# SH_HALF_ab_3.net
KiCad netlist of a schematic drawn in EAGLE
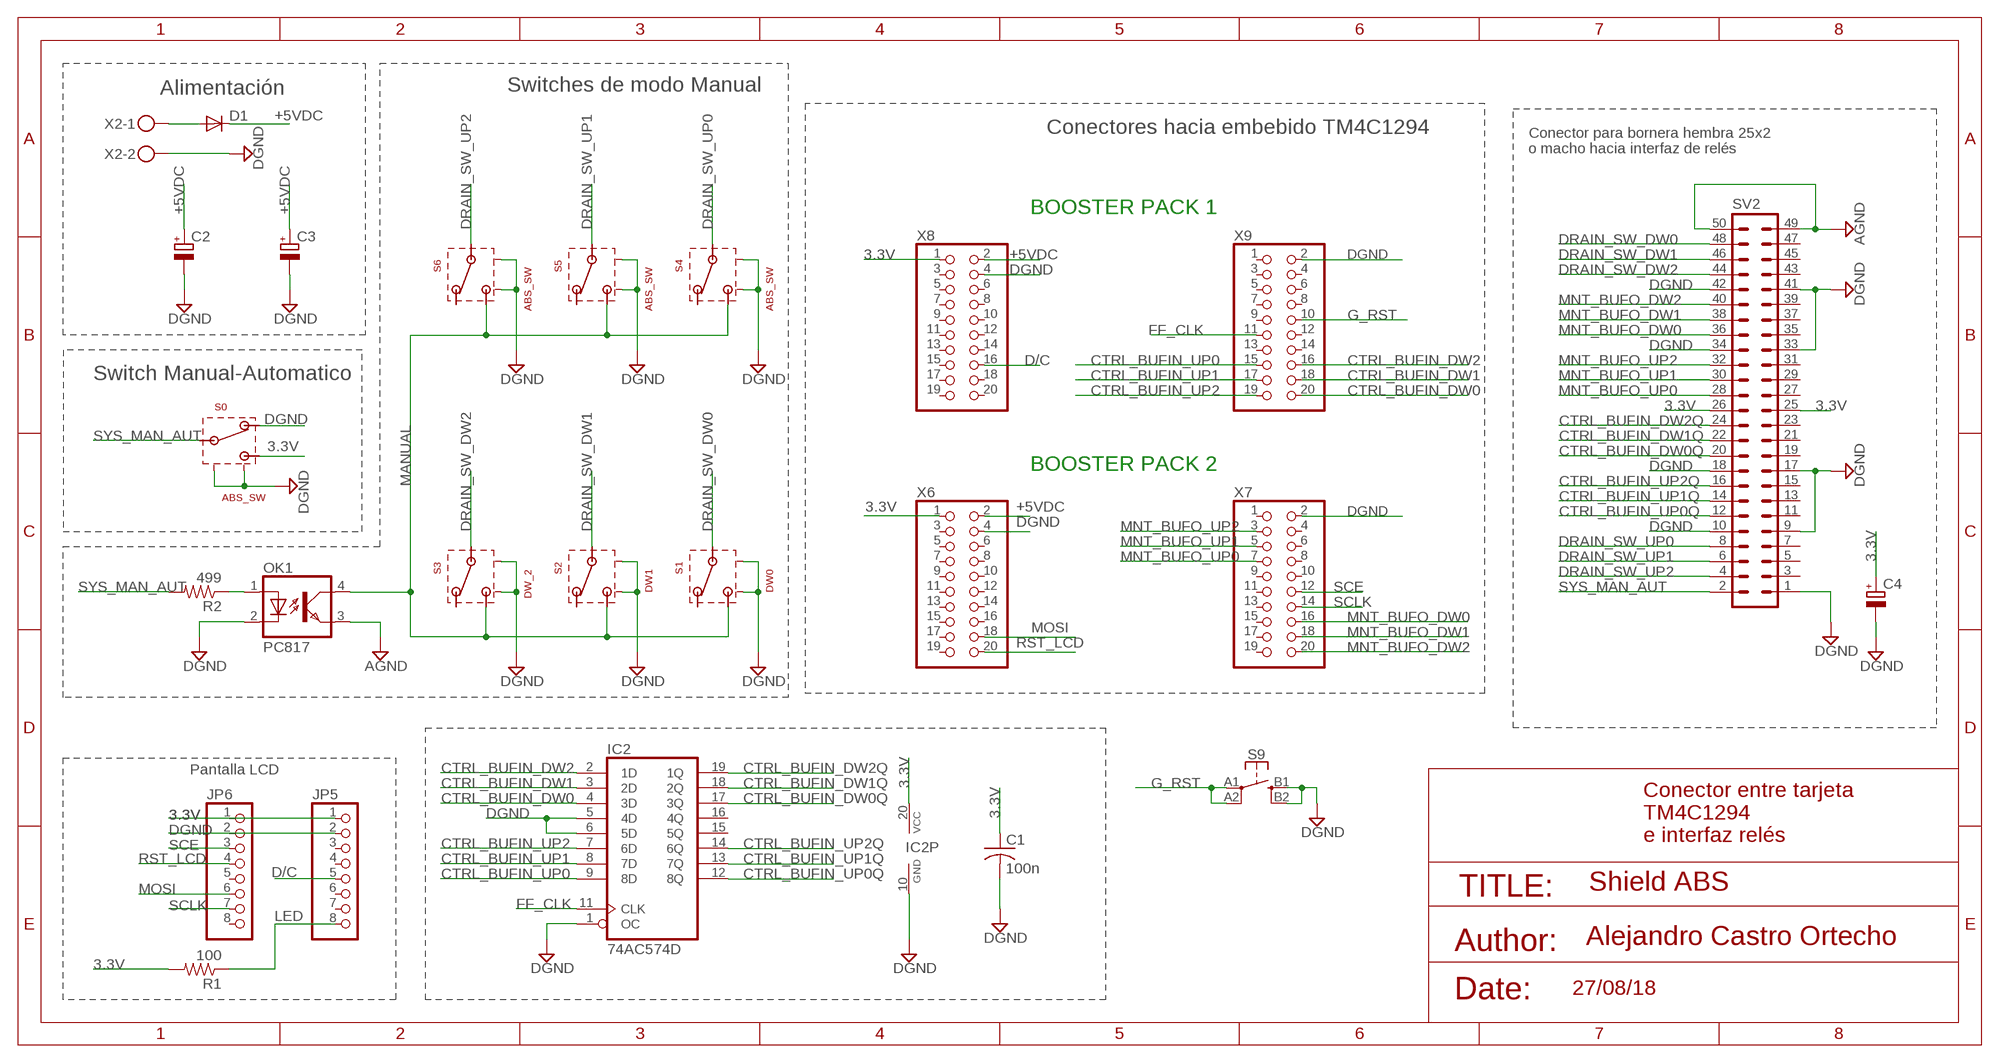
[diagram p0: schematic, sheet 1]

(export (version "E")
  (design (tool "Eeschema 10.0.6"))
  (components
    (comp (ref "C1")
      (value "100n")
      (footprint "eagle-import:C0805K")
      (libsource (lib "eagle-import") (part "C-USC0805K"))
    )
    (comp (ref "C2")
      (value "CPOL-EUB/3528-21R")
      (footprint "eagle-import:B_3528-21R")
      (libsource (lib "eagle-import") (part "CPOL-EUB/3528-21R"))
    )
    (comp (ref "C3")
      (value "CPOL-EUB/3528-21R")
      (footprint "eagle-import:B_3528-21R")
      (libsource (lib "eagle-import") (part "CPOL-EUB/3528-21R"))
    )
    (comp (ref "C4")
      (value "CPOL-EUB/3528-21R")
      (footprint "eagle-import:B_3528-21R")
      (libsource (lib "eagle-import") (part "CPOL-EUB/3528-21R"))
    )
    (comp (ref "D1")
      (value "DIODE-SMBSMB")
      (footprint "eagle-import:SMB")
      (fields (field (name "MANF") "Diodes Incorporated"))
      (libsource (lib "eagle-import") (part "DIODE-SMBSMB"))
    )
    (comp (ref "IC2")
      (value "74AC574D")
      (footprint "eagle-import:SO20W")
      (libsource (lib "eagle-import") (part "74574DAC"))
    )
    (comp (ref "JP5")
      (value "PINHD-1X8")
      (footprint "eagle-import:1X08")
      (libsource (lib "eagle-import") (part "PINHD-1X8"))
    )
    (comp (ref "JP6")
      (value "PINHD-1X8")
      (footprint "eagle-import:1X08")
      (libsource (lib "eagle-import") (part "PINHD-1X8"))
    )
    (comp (ref "OK1")
      (value "PC817")
      (footprint "eagle-import:DIL04")
      (fields (field (name "MPN") "PC817X4J000F"))
      (libsource (lib "eagle-import") (part "PC817"))
    )
    (comp (ref "R1")
      (value "100")
      (footprint "eagle-import:R1206")
      (libsource (lib "eagle-import") (part "R-US_R1206"))
    )
    (comp (ref "R2")
      (value "499")
      (footprint "eagle-import:R1206")
      (libsource (lib "eagle-import") (part "R-US_R1206"))
    )
    (comp (ref "S0")
      (value "ABS_SW")
      (footprint "eagle-import:ABS_SW")
      (libsource (lib "eagle-import") (part "ABS_SW"))
    )
    (comp (ref "S1")
      (value "DW0")
      (footprint "eagle-import:ABS_SW")
      (libsource (lib "eagle-import") (part "ABS_SW"))
    )
    (comp (ref "S2")
      (value "DW1")
      (footprint "eagle-import:ABS_SW")
      (libsource (lib "eagle-import") (part "ABS_SW"))
    )
    (comp (ref "S3")
      (value "DW_2")
      (footprint "eagle-import:ABS_SW")
      (libsource (lib "eagle-import") (part "ABS_SW"))
    )
    (comp (ref "S4")
      (value "ABS_SW")
      (footprint "eagle-import:ABS_SW")
      (libsource (lib "eagle-import") (part "ABS_SW"))
    )
    (comp (ref "S5")
      (value "ABS_SW")
      (footprint "eagle-import:ABS_SW")
      (libsource (lib "eagle-import") (part "ABS_SW"))
    )
    (comp (ref "S6")
      (value "ABS_SW")
      (footprint "eagle-import:ABS_SW")
      (libsource (lib "eagle-import") (part "ABS_SW"))
    )
    (comp (ref "S9")
      (value "MOMENTARY-SWITCH-SPST-2")
      (footprint "eagle-import:TACTILE_SWITCH_SMD_6.2MM_TALL")
      (libsource (lib "eagle-import") (part "MOMENTARY-SWITCH-SPST-2"))
    )
    (comp (ref "SV2")
      (value "ML50F")
      (footprint "eagle-import:ML50_F")
      (libsource (lib "eagle-import") (part "ML50F"))
    )
    (comp (ref "X2")
      (value "MKDSN1,5/2-5,08")
      (footprint "eagle-import:MKDSN1,5_2-5,08")
      (libsource (lib "eagle-import") (part "MKDSN1,5/2-5,08"))
    )
    (comp (ref "X6")
      (value "PINHD-2X10")
      (footprint "eagle-import:2X10")
      (libsource (lib "eagle-import") (part "PINHD-2X10"))
    )
    (comp (ref "X7")
      (value "PINHD-2X10")
      (footprint "eagle-import:2X10")
      (libsource (lib "eagle-import") (part "PINHD-2X10"))
    )
    (comp (ref "X8")
      (value "PINHD-2X10")
      (footprint "eagle-import:2X10")
      (libsource (lib "eagle-import") (part "PINHD-2X10"))
    )
    (comp (ref "X9")
      (value "PINHD-2X10")
      (footprint "eagle-import:2X10")
      (libsource (lib "eagle-import") (part "PINHD-2X10"))
    )
  )
  (nets
    (net (code "1") (name "/+5VDC") (class "Default")
      (node (ref "C2") (pin "+") (pinfunction "+_+") (pintype "passive"))
      (node (ref "C3") (pin "+") (pinfunction "+_+") (pintype "passive"))
      (node (ref "D1") (pin "C") (pinfunction "C_C") (pintype "passive"))
      (node (ref "X6") (pin "2") (pinfunction "2_2") (pintype "passive"))
      (node (ref "X8") (pin "2") (pinfunction "2_2") (pintype "passive"))
    )
    (net (code "2") (name "/3.3V") (class "Default")
      (node (ref "C1") (pin "1") (pinfunction "1_1") (pintype "passive"))
      (node (ref "C4") (pin "+") (pinfunction "+_+") (pintype "passive"))
      (node (ref "IC2") (pin "20") (pinfunction "VCC_20") (pintype "power_in"))
      (node (ref "JP5") (pin "1") (pinfunction "1_1") (pintype "passive"))
      (node (ref "JP6") (pin "1") (pinfunction "1_1") (pintype "passive"))
      (node (ref "R1") (pin "2") (pinfunction "2_2") (pintype "passive"))
      (node (ref "S0") (pin "3") (pinfunction "3_3") (pintype "bidirectional"))
      (node (ref "SV2") (pin "25") (pinfunction "25_25") (pintype "passive"))
      (node (ref "SV2") (pin "26") (pinfunction "26_26") (pintype "passive"))
      (node (ref "X6") (pin "1") (pinfunction "1_1") (pintype "passive"))
      (node (ref "X8") (pin "1") (pinfunction "1_1") (pintype "passive"))
    )
    (net (code "3") (name "/CTRL_BUFIN_DW0") (class "Default")
      (node (ref "IC2") (pin "4") (pinfunction "3D_4") (pintype "input"))
      (node (ref "X9") (pin "20") (pinfunction "20_20") (pintype "passive"))
    )
    (net (code "4") (name "/CTRL_BUFIN_DW0Q") (class "Default")
      (node (ref "IC2") (pin "17") (pinfunction "3Q_17") (pintype "tri_state"))
      (node (ref "SV2") (pin "20") (pinfunction "20_20") (pintype "passive"))
    )
    (net (code "5") (name "/CTRL_BUFIN_DW1") (class "Default")
      (node (ref "IC2") (pin "3") (pinfunction "2D_3") (pintype "input"))
      (node (ref "X9") (pin "18") (pinfunction "18_18") (pintype "passive"))
    )
    (net (code "6") (name "/CTRL_BUFIN_DW1Q") (class "Default")
      (node (ref "IC2") (pin "18") (pinfunction "2Q_18") (pintype "tri_state"))
      (node (ref "SV2") (pin "22") (pinfunction "22_22") (pintype "passive"))
    )
    (net (code "7") (name "/CTRL_BUFIN_DW2") (class "Default")
      (node (ref "IC2") (pin "2") (pinfunction "1D_2") (pintype "input"))
      (node (ref "X9") (pin "16") (pinfunction "16_16") (pintype "passive"))
    )
    (net (code "8") (name "/CTRL_BUFIN_DW2Q") (class "Default")
      (node (ref "IC2") (pin "19") (pinfunction "1Q_19") (pintype "tri_state"))
      (node (ref "SV2") (pin "24") (pinfunction "24_24") (pintype "passive"))
    )
    (net (code "9") (name "/CTRL_BUFIN_UP0") (class "Default")
      (node (ref "IC2") (pin "9") (pinfunction "8D_9") (pintype "input"))
      (node (ref "X9") (pin "15") (pinfunction "15_15") (pintype "passive"))
    )
    (net (code "10") (name "/CTRL_BUFIN_UP0Q") (class "Default")
      (node (ref "IC2") (pin "12") (pinfunction "8Q_12") (pintype "tri_state"))
      (node (ref "SV2") (pin "12") (pinfunction "12_12") (pintype "passive"))
    )
    (net (code "11") (name "/CTRL_BUFIN_UP1") (class "Default")
      (node (ref "IC2") (pin "8") (pinfunction "7D_8") (pintype "input"))
      (node (ref "X9") (pin "17") (pinfunction "17_17") (pintype "passive"))
    )
    (net (code "12") (name "/CTRL_BUFIN_UP1Q") (class "Default")
      (node (ref "IC2") (pin "13") (pinfunction "7Q_13") (pintype "tri_state"))
      (node (ref "SV2") (pin "14") (pinfunction "14_14") (pintype "passive"))
    )
    (net (code "13") (name "/CTRL_BUFIN_UP2") (class "Default")
      (node (ref "IC2") (pin "7") (pinfunction "6D_7") (pintype "input"))
      (node (ref "X9") (pin "19") (pinfunction "19_19") (pintype "passive"))
    )
    (net (code "14") (name "/CTRL_BUFIN_UP2Q") (class "Default")
      (node (ref "IC2") (pin "14") (pinfunction "6Q_14") (pintype "tri_state"))
      (node (ref "SV2") (pin "16") (pinfunction "16_16") (pintype "passive"))
    )
    (net (code "15") (name "/DRAIN_SW_DW0") (class "Default")
      (node (ref "S1") (pin "2") (pinfunction "2_2") (pintype "bidirectional"))
      (node (ref "SV2") (pin "48") (pinfunction "48_48") (pintype "passive"))
    )
    (net (code "16") (name "/DRAIN_SW_DW1") (class "Default")
      (node (ref "S2") (pin "2") (pinfunction "2_2") (pintype "bidirectional"))
      (node (ref "SV2") (pin "46") (pinfunction "46_46") (pintype "passive"))
    )
    (net (code "17") (name "/DRAIN_SW_DW2") (class "Default")
      (node (ref "S3") (pin "2") (pinfunction "2_2") (pintype "bidirectional"))
      (node (ref "SV2") (pin "44") (pinfunction "44_44") (pintype "passive"))
    )
    (net (code "18") (name "/DRAIN_SW_UP0") (class "Default")
      (node (ref "S4") (pin "2") (pinfunction "2_2") (pintype "bidirectional"))
      (node (ref "SV2") (pin "8") (pinfunction "8_8") (pintype "passive"))
    )
    (net (code "19") (name "/DRAIN_SW_UP1") (class "Default")
      (node (ref "S5") (pin "2") (pinfunction "2_2") (pintype "bidirectional"))
      (node (ref "SV2") (pin "6") (pinfunction "6_6") (pintype "passive"))
    )
    (net (code "20") (name "/DRAIN_SW_UP2") (class "Default")
      (node (ref "S6") (pin "2") (pinfunction "2_2") (pintype "bidirectional"))
      (node (ref "SV2") (pin "4") (pinfunction "4_4") (pintype "passive"))
    )
    (net (code "21") (name "/D{slash}C") (class "Default")
      (node (ref "JP5") (pin "5") (pinfunction "5_5") (pintype "passive"))
      (node (ref "X8") (pin "16") (pinfunction "16_16") (pintype "passive"))
    )
    (net (code "22") (name "/FF_CLK") (class "Default")
      (node (ref "IC2") (pin "11") (pinfunction "CLK_11") (pintype "input"))
      (node (ref "X9") (pin "11") (pinfunction "11_11") (pintype "passive"))
    )
    (net (code "23") (name "/G_RST") (class "Default")
      (node (ref "S9") (pin "A1") (pinfunction "1_A1") (pintype "passive"))
      (node (ref "S9") (pin "A2") (pinfunction "2_A2") (pintype "passive"))
      (node (ref "X9") (pin "10") (pinfunction "10_10") (pintype "passive"))
    )
    (net (code "24") (name "/LED") (class "Default")
      (node (ref "JP5") (pin "8") (pinfunction "8_8") (pintype "passive"))
      (node (ref "R1") (pin "1") (pinfunction "1_1") (pintype "passive"))
    )
    (net (code "25") (name "/MANUAL") (class "Default")
      (node (ref "OK1") (pin "4") (pinfunction "COL_4") (pintype "passive"))
      (node (ref "S1") (pin "3") (pinfunction "3_3") (pintype "bidirectional"))
      (node (ref "S2") (pin "3") (pinfunction "3_3") (pintype "bidirectional"))
      (node (ref "S3") (pin "3") (pinfunction "3_3") (pintype "bidirectional"))
      (node (ref "S4") (pin "3") (pinfunction "3_3") (pintype "bidirectional"))
      (node (ref "S5") (pin "3") (pinfunction "3_3") (pintype "bidirectional"))
      (node (ref "S6") (pin "3") (pinfunction "3_3") (pintype "bidirectional"))
    )
    (net (code "26") (name "/MNT_BUFO_DW0") (class "Default")
      (node (ref "SV2") (pin "36") (pinfunction "36_36") (pintype "passive"))
      (node (ref "X7") (pin "16") (pinfunction "16_16") (pintype "passive"))
    )
    (net (code "27") (name "/MNT_BUFO_DW1") (class "Default")
      (node (ref "SV2") (pin "38") (pinfunction "38_38") (pintype "passive"))
      (node (ref "X7") (pin "18") (pinfunction "18_18") (pintype "passive"))
    )
    (net (code "28") (name "/MNT_BUFO_DW2") (class "Default")
      (node (ref "SV2") (pin "40") (pinfunction "40_40") (pintype "passive"))
      (node (ref "X7") (pin "20") (pinfunction "20_20") (pintype "passive"))
    )
    (net (code "29") (name "/MNT_BUFO_UP0") (class "Default")
      (node (ref "SV2") (pin "28") (pinfunction "28_28") (pintype "passive"))
      (node (ref "X7") (pin "7") (pinfunction "7_7") (pintype "passive"))
    )
    (net (code "30") (name "/MNT_BUFO_UP1") (class "Default")
      (node (ref "SV2") (pin "30") (pinfunction "30_30") (pintype "passive"))
      (node (ref "X7") (pin "5") (pinfunction "5_5") (pintype "passive"))
    )
    (net (code "31") (name "/MNT_BUFO_UP2") (class "Default")
      (node (ref "SV2") (pin "32") (pinfunction "32_32") (pintype "passive"))
      (node (ref "X7") (pin "3") (pinfunction "3_3") (pintype "passive"))
    )
    (net (code "32") (name "/MOSI") (class "Default")
      (node (ref "JP6") (pin "6") (pinfunction "6_6") (pintype "passive"))
      (node (ref "X6") (pin "18") (pinfunction "18_18") (pintype "passive"))
    )
    (net (code "33") (name "/RST_LCD") (class "Default")
      (node (ref "JP6") (pin "4") (pinfunction "4_4") (pintype "passive"))
      (node (ref "X6") (pin "20") (pinfunction "20_20") (pintype "passive"))
    )
    (net (code "34") (name "/SCE") (class "Default")
      (node (ref "JP6") (pin "3") (pinfunction "3_3") (pintype "passive"))
      (node (ref "X7") (pin "12") (pinfunction "12_12") (pintype "passive"))
    )
    (net (code "35") (name "/SCLK") (class "Default")
      (node (ref "JP6") (pin "7") (pinfunction "7_7") (pintype "passive"))
      (node (ref "X7") (pin "14") (pinfunction "14_14") (pintype "passive"))
    )
    (net (code "36") (name "/SYS_MAN_AUT") (class "Default")
      (node (ref "R2") (pin "2") (pinfunction "2_2") (pintype "passive"))
      (node (ref "S0") (pin "2") (pinfunction "2_2") (pintype "bidirectional"))
      (node (ref "SV2") (pin "2") (pinfunction "2_2") (pintype "passive"))
    )
    (net (code "37") (name "AGND") (class "Default")
      (node (ref "OK1") (pin "3") (pinfunction "EMIT_3") (pintype "passive"))
      (node (ref "SV2") (pin "49") (pinfunction "49_49") (pintype "passive"))
      (node (ref "SV2") (pin "50") (pinfunction "50_50") (pintype "passive"))
    )
    (net (code "38") (name "DGND") (class "Default")
      (node (ref "C1") (pin "2") (pinfunction "2_2") (pintype "passive"))
      (node (ref "C2") (pin "-") (pinfunction "-_-") (pintype "passive"))
      (node (ref "C3") (pin "-") (pinfunction "-_-") (pintype "passive"))
      (node (ref "C4") (pin "-") (pinfunction "-_-") (pintype "passive"))
      (node (ref "IC2") (pin "1") (pinfunction "OC_1") (pintype "input"))
      (node (ref "IC2") (pin "10") (pinfunction "GND_10") (pintype "power_in"))
      (node (ref "IC2") (pin "5") (pinfunction "4D_5") (pintype "input"))
      (node (ref "IC2") (pin "6") (pinfunction "5D_6") (pintype "input"))
      (node (ref "JP5") (pin "2") (pinfunction "2_2") (pintype "passive"))
      (node (ref "JP6") (pin "2") (pinfunction "2_2") (pintype "passive"))
      (node (ref "OK1") (pin "2") (pinfunction "C_2") (pintype "passive"))
      (node (ref "S0") (pin "1") (pinfunction "1_1") (pintype "bidirectional"))
      (node (ref "S0") (pin "M1") (pinfunction "GND_M1") (pintype "power_in"))
      (node (ref "S0") (pin "M2") (pinfunction "GND1_M2") (pintype "power_in"))
      (node (ref "S1") (pin "M1") (pinfunction "GND_M1") (pintype "power_in"))
      (node (ref "S1") (pin "M2") (pinfunction "GND1_M2") (pintype "power_in"))
      (node (ref "S2") (pin "M1") (pinfunction "GND_M1") (pintype "power_in"))
      (node (ref "S2") (pin "M2") (pinfunction "GND1_M2") (pintype "power_in"))
      (node (ref "S3") (pin "M1") (pinfunction "GND_M1") (pintype "power_in"))
      (node (ref "S3") (pin "M2") (pinfunction "GND1_M2") (pintype "power_in"))
      (node (ref "S4") (pin "M1") (pinfunction "GND_M1") (pintype "power_in"))
      (node (ref "S4") (pin "M2") (pinfunction "GND1_M2") (pintype "power_in"))
      (node (ref "S5") (pin "M1") (pinfunction "GND_M1") (pintype "power_in"))
      (node (ref "S5") (pin "M2") (pinfunction "GND1_M2") (pintype "power_in"))
      (node (ref "S6") (pin "M1") (pinfunction "GND_M1") (pintype "power_in"))
      (node (ref "S6") (pin "M2") (pinfunction "GND1_M2") (pintype "power_in"))
      (node (ref "S9") (pin "B1") (pinfunction "3_B1") (pintype "passive"))
      (node (ref "S9") (pin "B2") (pinfunction "4_B2") (pintype "passive"))
      (node (ref "SV2") (pin "1") (pinfunction "1_1") (pintype "passive"))
      (node (ref "SV2") (pin "10") (pinfunction "10_10") (pintype "passive"))
      (node (ref "SV2") (pin "17") (pinfunction "17_17") (pintype "passive"))
      (node (ref "SV2") (pin "18") (pinfunction "18_18") (pintype "passive"))
      (node (ref "SV2") (pin "33") (pinfunction "33_33") (pintype "passive"))
      (node (ref "SV2") (pin "34") (pinfunction "34_34") (pintype "passive"))
      (node (ref "SV2") (pin "41") (pinfunction "41_41") (pintype "passive"))
      (node (ref "SV2") (pin "42") (pinfunction "42_42") (pintype "passive"))
      (node (ref "SV2") (pin "9") (pinfunction "9_9") (pintype "passive"))
      (node (ref "X2") (pin "2") (pinfunction "KL_2") (pintype "passive"))
      (node (ref "X6") (pin "4") (pinfunction "4_4") (pintype "passive"))
      (node (ref "X7") (pin "2") (pinfunction "2_2") (pintype "passive"))
      (node (ref "X8") (pin "4") (pinfunction "4_4") (pintype "passive"))
      (node (ref "X9") (pin "2") (pinfunction "2_2") (pintype "passive"))
    )
    (net (code "39") (name "Net-(OK1-A)") (class "Default")
      (node (ref "OK1") (pin "1") (pinfunction "A_1") (pintype "passive"))
      (node (ref "R2") (pin "1") (pinfunction "1_1") (pintype "passive"))
    )
    (net (code "40") (name "Net-(X2A-KL)") (class "Default")
      (node (ref "D1") (pin "A") (pinfunction "A_A") (pintype "passive"))
      (node (ref "X2") (pin "1") (pinfunction "KL_1") (pintype "passive"))
    )
    (net (code "41") (name "unconnected-(IC2A-4Q-Pad16)") (class "Default")
      (node (ref "IC2") (pin "16") (pinfunction "4Q_16") (pintype "tri_state"))
    )
    (net (code "42") (name "unconnected-(IC2A-5Q-Pad15)") (class "Default")
      (node (ref "IC2") (pin "15") (pinfunction "5Q_15") (pintype "tri_state"))
    )
    (net (code "43") (name "unconnected-(JP5-Pad3)") (class "Default")
      (node (ref "JP5") (pin "3") (pinfunction "3_3") (pintype "passive"))
    )
    (net (code "44") (name "unconnected-(JP5-Pad4)") (class "Default")
      (node (ref "JP5") (pin "4") (pinfunction "4_4") (pintype "passive"))
    )
    (net (code "45") (name "unconnected-(JP5-Pad6)") (class "Default")
      (node (ref "JP5") (pin "6") (pinfunction "6_6") (pintype "passive"))
    )
    (net (code "46") (name "unconnected-(JP5-Pad7)") (class "Default")
      (node (ref "JP5") (pin "7") (pinfunction "7_7") (pintype "passive"))
    )
    (net (code "47") (name "unconnected-(JP6-Pad5)") (class "Default")
      (node (ref "JP6") (pin "5") (pinfunction "5_5") (pintype "passive"))
    )
    (net (code "48") (name "unconnected-(JP6-Pad8)") (class "Default")
      (node (ref "JP6") (pin "8") (pinfunction "8_8") (pintype "passive"))
    )
    (net (code "49") (name "unconnected-(S1-Pad1)") (class "Default")
      (node (ref "S1") (pin "1") (pinfunction "1_1") (pintype "bidirectional"))
    )
    (net (code "50") (name "unconnected-(S2-Pad1)") (class "Default")
      (node (ref "S2") (pin "1") (pinfunction "1_1") (pintype "bidirectional"))
    )
    (net (code "51") (name "unconnected-(S3-Pad1)") (class "Default")
      (node (ref "S3") (pin "1") (pinfunction "1_1") (pintype "bidirectional"))
    )
    (net (code "52") (name "unconnected-(S4-Pad1)") (class "Default")
      (node (ref "S4") (pin "1") (pinfunction "1_1") (pintype "bidirectional"))
    )
    (net (code "53") (name "unconnected-(S5-Pad1)") (class "Default")
      (node (ref "S5") (pin "1") (pinfunction "1_1") (pintype "bidirectional"))
    )
    (net (code "54") (name "unconnected-(S6-Pad1)") (class "Default")
      (node (ref "S6") (pin "1") (pinfunction "1_1") (pintype "bidirectional"))
    )
    (net (code "55") (name "unconnected-(SV2-Pad3)") (class "Default")
      (node (ref "SV2") (pin "3") (pinfunction "3_3") (pintype "passive"))
    )
    (net (code "56") (name "unconnected-(SV2-Pad5)") (class "Default")
      (node (ref "SV2") (pin "5") (pinfunction "5_5") (pintype "passive"))
    )
    (net (code "57") (name "unconnected-(SV2-Pad7)") (class "Default")
      (node (ref "SV2") (pin "7") (pinfunction "7_7") (pintype "passive"))
    )
    (net (code "58") (name "unconnected-(SV2-Pad11)") (class "Default")
      (node (ref "SV2") (pin "11") (pinfunction "11_11") (pintype "passive"))
    )
    (net (code "59") (name "unconnected-(SV2-Pad13)") (class "Default")
      (node (ref "SV2") (pin "13") (pinfunction "13_13") (pintype "passive"))
    )
    (net (code "60") (name "unconnected-(SV2-Pad15)") (class "Default")
      (node (ref "SV2") (pin "15") (pinfunction "15_15") (pintype "passive"))
    )
    (net (code "61") (name "unconnected-(SV2-Pad19)") (class "Default")
      (node (ref "SV2") (pin "19") (pinfunction "19_19") (pintype "passive"))
    )
    (net (code "62") (name "unconnected-(SV2-Pad21)") (class "Default")
      (node (ref "SV2") (pin "21") (pinfunction "21_21") (pintype "passive"))
    )
    (net (code "63") (name "unconnected-(SV2-Pad23)") (class "Default")
      (node (ref "SV2") (pin "23") (pinfunction "23_23") (pintype "passive"))
    )
    (net (code "64") (name "unconnected-(SV2-Pad27)") (class "Default")
      (node (ref "SV2") (pin "27") (pinfunction "27_27") (pintype "passive"))
    )
    (net (code "65") (name "unconnected-(SV2-Pad29)") (class "Default")
      (node (ref "SV2") (pin "29") (pinfunction "29_29") (pintype "passive"))
    )
    (net (code "66") (name "unconnected-(SV2-Pad31)") (class "Default")
      (node (ref "SV2") (pin "31") (pinfunction "31_31") (pintype "passive"))
    )
    (net (code "67") (name "unconnected-(SV2-Pad35)") (class "Default")
      (node (ref "SV2") (pin "35") (pinfunction "35_35") (pintype "passive"))
    )
    (net (code "68") (name "unconnected-(SV2-Pad37)") (class "Default")
      (node (ref "SV2") (pin "37") (pinfunction "37_37") (pintype "passive"))
    )
    (net (code "69") (name "unconnected-(SV2-Pad39)") (class "Default")
      (node (ref "SV2") (pin "39") (pinfunction "39_39") (pintype "passive"))
    )
    (net (code "70") (name "unconnected-(SV2-Pad43)") (class "Default")
      (node (ref "SV2") (pin "43") (pinfunction "43_43") (pintype "passive"))
    )
    (net (code "71") (name "unconnected-(SV2-Pad45)") (class "Default")
      (node (ref "SV2") (pin "45") (pinfunction "45_45") (pintype "passive"))
    )
    (net (code "72") (name "unconnected-(SV2-Pad47)") (class "Default")
      (node (ref "SV2") (pin "47") (pinfunction "47_47") (pintype "passive"))
    )
    (net (code "73") (name "unconnected-(X6-Pad3)") (class "Default")
      (node (ref "X6") (pin "3") (pinfunction "3_3") (pintype "passive"))
    )
    (net (code "74") (name "unconnected-(X6-Pad5)") (class "Default")
      (node (ref "X6") (pin "5") (pinfunction "5_5") (pintype "passive"))
    )
    (net (code "75") (name "unconnected-(X6-Pad6)") (class "Default")
      (node (ref "X6") (pin "6") (pinfunction "6_6") (pintype "passive"))
    )
    (net (code "76") (name "unconnected-(X6-Pad7)") (class "Default")
      (node (ref "X6") (pin "7") (pinfunction "7_7") (pintype "passive"))
    )
    (net (code "77") (name "unconnected-(X6-Pad8)") (class "Default")
      (node (ref "X6") (pin "8") (pinfunction "8_8") (pintype "passive"))
    )
    (net (code "78") (name "unconnected-(X6-Pad9)") (class "Default")
      (node (ref "X6") (pin "9") (pinfunction "9_9") (pintype "passive"))
    )
    (net (code "79") (name "unconnected-(X6-Pad10)") (class "Default")
      (node (ref "X6") (pin "10") (pinfunction "10_10") (pintype "passive"))
    )
    (net (code "80") (name "unconnected-(X6-Pad11)") (class "Default")
      (node (ref "X6") (pin "11") (pinfunction "11_11") (pintype "passive"))
    )
    (net (code "81") (name "unconnected-(X6-Pad12)") (class "Default")
      (node (ref "X6") (pin "12") (pinfunction "12_12") (pintype "passive"))
    )
    (net (code "82") (name "unconnected-(X6-Pad13)") (class "Default")
      (node (ref "X6") (pin "13") (pinfunction "13_13") (pintype "passive"))
    )
    (net (code "83") (name "unconnected-(X6-Pad14)") (class "Default")
      (node (ref "X6") (pin "14") (pinfunction "14_14") (pintype "passive"))
    )
    (net (code "84") (name "unconnected-(X6-Pad15)") (class "Default")
      (node (ref "X6") (pin "15") (pinfunction "15_15") (pintype "passive"))
    )
    (net (code "85") (name "unconnected-(X6-Pad16)") (class "Default")
      (node (ref "X6") (pin "16") (pinfunction "16_16") (pintype "passive"))
    )
    (net (code "86") (name "unconnected-(X6-Pad17)") (class "Default")
      (node (ref "X6") (pin "17") (pinfunction "17_17") (pintype "passive"))
    )
    (net (code "87") (name "unconnected-(X6-Pad19)") (class "Default")
      (node (ref "X6") (pin "19") (pinfunction "19_19") (pintype "passive"))
    )
    (net (code "88") (name "unconnected-(X7-Pad1)") (class "Default")
      (node (ref "X7") (pin "1") (pinfunction "1_1") (pintype "passive"))
    )
    (net (code "89") (name "unconnected-(X7-Pad4)") (class "Default")
      (node (ref "X7") (pin "4") (pinfunction "4_4") (pintype "passive"))
    )
    (net (code "90") (name "unconnected-(X7-Pad6)") (class "Default")
      (node (ref "X7") (pin "6") (pinfunction "6_6") (pintype "passive"))
    )
    (net (code "91") (name "unconnected-(X7-Pad8)") (class "Default")
      (node (ref "X7") (pin "8") (pinfunction "8_8") (pintype "passive"))
    )
    (net (code "92") (name "unconnected-(X7-Pad9)") (class "Default")
      (node (ref "X7") (pin "9") (pinfunction "9_9") (pintype "passive"))
    )
    (net (code "93") (name "unconnected-(X7-Pad10)") (class "Default")
      (node (ref "X7") (pin "10") (pinfunction "10_10") (pintype "passive"))
    )
    (net (code "94") (name "unconnected-(X7-Pad11)") (class "Default")
      (node (ref "X7") (pin "11") (pinfunction "11_11") (pintype "passive"))
    )
    (net (code "95") (name "unconnected-(X7-Pad13)") (class "Default")
      (node (ref "X7") (pin "13") (pinfunction "13_13") (pintype "passive"))
    )
    (net (code "96") (name "unconnected-(X7-Pad15)") (class "Default")
      (node (ref "X7") (pin "15") (pinfunction "15_15") (pintype "passive"))
    )
    (net (code "97") (name "unconnected-(X7-Pad17)") (class "Default")
      (node (ref "X7") (pin "17") (pinfunction "17_17") (pintype "passive"))
    )
    (net (code "98") (name "unconnected-(X7-Pad19)") (class "Default")
      (node (ref "X7") (pin "19") (pinfunction "19_19") (pintype "passive"))
    )
    (net (code "99") (name "unconnected-(X8-Pad3)") (class "Default")
      (node (ref "X8") (pin "3") (pinfunction "3_3") (pintype "passive"))
    )
    (net (code "100") (name "unconnected-(X8-Pad5)") (class "Default")
      (node (ref "X8") (pin "5") (pinfunction "5_5") (pintype "passive"))
    )
    (net (code "101") (name "unconnected-(X8-Pad6)") (class "Default")
      (node (ref "X8") (pin "6") (pinfunction "6_6") (pintype "passive"))
    )
    (net (code "102") (name "unconnected-(X8-Pad7)") (class "Default")
      (node (ref "X8") (pin "7") (pinfunction "7_7") (pintype "passive"))
    )
    (net (code "103") (name "unconnected-(X8-Pad8)") (class "Default")
      (node (ref "X8") (pin "8") (pinfunction "8_8") (pintype "passive"))
    )
    (net (code "104") (name "unconnected-(X8-Pad9)") (class "Default")
      (node (ref "X8") (pin "9") (pinfunction "9_9") (pintype "passive"))
    )
    (net (code "105") (name "unconnected-(X8-Pad10)") (class "Default")
      (node (ref "X8") (pin "10") (pinfunction "10_10") (pintype "passive"))
    )
    (net (code "106") (name "unconnected-(X8-Pad11)") (class "Default")
      (node (ref "X8") (pin "11") (pinfunction "11_11") (pintype "passive"))
    )
    (net (code "107") (name "unconnected-(X8-Pad12)") (class "Default")
      (node (ref "X8") (pin "12") (pinfunction "12_12") (pintype "passive"))
    )
    (net (code "108") (name "unconnected-(X8-Pad13)") (class "Default")
      (node (ref "X8") (pin "13") (pinfunction "13_13") (pintype "passive"))
    )
    (net (code "109") (name "unconnected-(X8-Pad14)") (class "Default")
      (node (ref "X8") (pin "14") (pinfunction "14_14") (pintype "passive"))
    )
    (net (code "110") (name "unconnected-(X8-Pad15)") (class "Default")
      (node (ref "X8") (pin "15") (pinfunction "15_15") (pintype "passive"))
    )
    (net (code "111") (name "unconnected-(X8-Pad17)") (class "Default")
      (node (ref "X8") (pin "17") (pinfunction "17_17") (pintype "passive"))
    )
    (net (code "112") (name "unconnected-(X8-Pad18)") (class "Default")
      (node (ref "X8") (pin "18") (pinfunction "18_18") (pintype "passive"))
    )
    (net (code "113") (name "unconnected-(X8-Pad19)") (class "Default")
      (node (ref "X8") (pin "19") (pinfunction "19_19") (pintype "passive"))
    )
    (net (code "114") (name "unconnected-(X8-Pad20)") (class "Default")
      (node (ref "X8") (pin "20") (pinfunction "20_20") (pintype "passive"))
    )
    (net (code "115") (name "unconnected-(X9-Pad1)") (class "Default")
      (node (ref "X9") (pin "1") (pinfunction "1_1") (pintype "passive"))
    )
    (net (code "116") (name "unconnected-(X9-Pad3)") (class "Default")
      (node (ref "X9") (pin "3") (pinfunction "3_3") (pintype "passive"))
    )
    (net (code "117") (name "unconnected-(X9-Pad4)") (class "Default")
      (node (ref "X9") (pin "4") (pinfunction "4_4") (pintype "passive"))
    )
    (net (code "118") (name "unconnected-(X9-Pad5)") (class "Default")
      (node (ref "X9") (pin "5") (pinfunction "5_5") (pintype "passive"))
    )
    (net (code "119") (name "unconnected-(X9-Pad6)") (class "Default")
      (node (ref "X9") (pin "6") (pinfunction "6_6") (pintype "passive"))
    )
    (net (code "120") (name "unconnected-(X9-Pad7)") (class "Default")
      (node (ref "X9") (pin "7") (pinfunction "7_7") (pintype "passive"))
    )
    (net (code "121") (name "unconnected-(X9-Pad8)") (class "Default")
      (node (ref "X9") (pin "8") (pinfunction "8_8") (pintype "passive"))
    )
    (net (code "122") (name "unconnected-(X9-Pad9)") (class "Default")
      (node (ref "X9") (pin "9") (pinfunction "9_9") (pintype "passive"))
    )
    (net (code "123") (name "unconnected-(X9-Pad12)") (class "Default")
      (node (ref "X9") (pin "12") (pinfunction "12_12") (pintype "passive"))
    )
    (net (code "124") (name "unconnected-(X9-Pad13)") (class "Default")
      (node (ref "X9") (pin "13") (pinfunction "13_13") (pintype "passive"))
    )
    (net (code "125") (name "unconnected-(X9-Pad14)") (class "Default")
      (node (ref "X9") (pin "14") (pinfunction "14_14") (pintype "passive"))
    )
  )
)
